# 08-USB_TF.net
KiCad netlist of a schematic drawn in Altium Designer
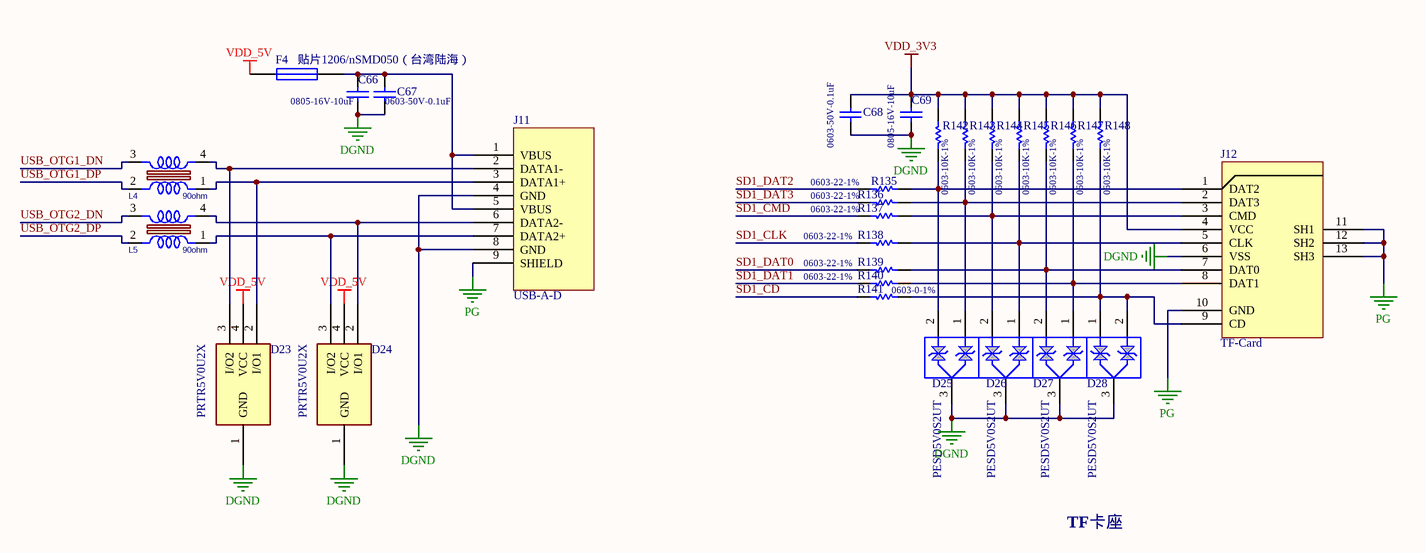
[diagram p0: 08-USB&TF.SchDoc]

(export (version "E")
  (design (tool "Eeschema 10.0.6"))
  (components
    (comp (ref "C66")
      (value "0805-16V-10uF")
      (footprint "0805C")
      (description "Capacitor")
      (fields (field (name "PUBLISHER") "Altium Limited"))
      (libsource (lib "Miscellaneous Devices") (part "Cap"))
    )
    (comp (ref "C67")
      (value "0603-50V-0.1uF")
      (footprint "0603C")
      (description "Capacitor")
      (fields (field (name "PUBLISHER") "Altium Limited"))
      (libsource (lib "Miscellaneous Devices") (part "Cap"))
    )
    (comp (ref "C68")
      (value "0603-50V-0.1uF")
      (footprint "0603C")
      (description "Capacitor")
      (fields (field (name "PUBLISHER") "Altium Limited"))
      (libsource (lib "Miscellaneous Devices") (part "Cap"))
    )
    (comp (ref "C69")
      (value "0805-16V-10uF")
      (footprint "0805C")
      (description "Capacitor")
      (fields (field (name "PUBLISHER") "Altium Limited"))
      (libsource (lib "Miscellaneous Devices") (part "Cap"))
    )
    (comp (ref "D23")
      (value "PRTR5V0U2X")
      (footprint "SOT-143")
      (description "PRTR5V0U2X,SOT-143B,NXP,RoHS")
      (libsource (lib "ErpMaterialData") (part "PRTR5V0U2X"))
    )
    (comp (ref "D24")
      (value "PRTR5V0U2X")
      (footprint "SOT-143")
      (description "PRTR5V0U2X,SOT-143B,NXP,RoHS")
      (libsource (lib "ErpMaterialData") (part "PRTR5V0U2X"))
    )
    (comp (ref "D25")
      (value "PESD5V0S2UT")
      (footprint "SOT-23")
      (description "TVS protect")
      (libsource (lib "*") (part "NUP2105L"))
    )
    (comp (ref "D26")
      (value "PESD5V0S2UT")
      (footprint "SOT-23")
      (description "TVS protect")
      (libsource (lib "*") (part "NUP2105L"))
    )
    (comp (ref "D27")
      (value "PESD5V0S2UT")
      (footprint "SOT-23")
      (description "TVS protect")
      (libsource (lib "*") (part "NUP2105L"))
    )
    (comp (ref "D28")
      (value "PESD5V0S2UT")
      (footprint "SOT-23")
      (description "TVS protect")
      (libsource (lib "*") (part "NUP2105L"))
    )
    (comp (ref "F4")
      (value "贴片1206/nSMD050（台湾陆海）")
      (footprint "1206F")
      (description "Fuse")
      (fields (field (name "PUBLISHER") "Altium Limited"))
      (libsource (lib "Miscellaneous Devices") (part "Fuse 1"))
    )
    (comp (ref "J11") (value "USB-A-D") (footprint "USB-AF-D") (libsource (lib "SCH-QQ") (part "USB-A-D")))
    (comp (ref "J12") (value "TF-Card") (footprint "SDCARD-M") (libsource (lib "Demos") (part "TF01A")))
    (comp (ref "L4")
      (value "90ohm")
      (footprint "indcm-sdcw2012")
      (description "共模电感")
      (libsource (lib "*") (part "Common Choke"))
    )
    (comp (ref "L5")
      (value "90ohm")
      (footprint "indcm-sdcw2012")
      (description "共模电感")
      (libsource (lib "*") (part "Common Choke"))
    )
    (comp (ref "R135")
      (value "0603-22-1%")
      (footprint "0603R")
      (description "Resistor")
      (fields (field (name "PUBLISHER") "Altium Limited"))
      (libsource (lib "Miscellaneous Devices") (part "Res1"))
    )
    (comp (ref "R136")
      (value "0603-22-1%")
      (footprint "0603R")
      (description "Resistor")
      (fields (field (name "PUBLISHER") "Altium Limited"))
      (libsource (lib "Miscellaneous Devices") (part "Res1"))
    )
    (comp (ref "R137")
      (value "0603-22-1%")
      (footprint "0603R")
      (description "Resistor")
      (fields (field (name "PUBLISHER") "Altium Limited"))
      (libsource (lib "Miscellaneous Devices") (part "Res1"))
    )
    (comp (ref "R138")
      (value "0603-22-1%")
      (footprint "0603R")
      (description "Resistor")
      (fields (field (name "PUBLISHER") "Altium Limited"))
      (libsource (lib "Miscellaneous Devices") (part "Res1"))
    )
    (comp (ref "R139")
      (value "0603-22-1%")
      (footprint "0603R")
      (description "Resistor")
      (fields (field (name "PUBLISHER") "Altium Limited"))
      (libsource (lib "Miscellaneous Devices") (part "Res1"))
    )
    (comp (ref "R140")
      (value "0603-22-1%")
      (footprint "0603R")
      (description "Resistor")
      (fields (field (name "PUBLISHER") "Altium Limited"))
      (libsource (lib "Miscellaneous Devices") (part "Res1"))
    )
    (comp (ref "R141")
      (value "0603-0-1%")
      (footprint "0603R")
      (description "Resistor")
      (fields (field (name "PUBLISHER") "Altium Limited"))
      (libsource (lib "Miscellaneous Devices") (part "Res1"))
    )
    (comp (ref "R142")
      (value "0603-10K-1%")
      (footprint "0603R")
      (description "Resistor")
      (fields (field (name "PUBLISHER") "Altium Limited"))
      (libsource (lib "Miscellaneous Devices") (part "Res1"))
    )
    (comp (ref "R143")
      (value "0603-10K-1%")
      (footprint "0603R")
      (description "Resistor")
      (fields (field (name "PUBLISHER") "Altium Limited"))
      (libsource (lib "Miscellaneous Devices") (part "Res1"))
    )
    (comp (ref "R144")
      (value "0603-10K-1%")
      (footprint "0603R")
      (description "Resistor")
      (fields (field (name "PUBLISHER") "Altium Limited"))
      (libsource (lib "Miscellaneous Devices") (part "Res1"))
    )
    (comp (ref "R145")
      (value "0603-10K-1%")
      (footprint "0603R")
      (description "Resistor")
      (fields (field (name "PUBLISHER") "Altium Limited"))
      (libsource (lib "Miscellaneous Devices") (part "Res1"))
    )
    (comp (ref "R146")
      (value "0603-10K-1%")
      (footprint "0603R")
      (description "Resistor")
      (fields (field (name "PUBLISHER") "Altium Limited"))
      (libsource (lib "Miscellaneous Devices") (part "Res1"))
    )
    (comp (ref "R147")
      (value "0603-10K-1%")
      (footprint "0603R")
      (description "Resistor")
      (fields (field (name "PUBLISHER") "Altium Limited"))
      (libsource (lib "Miscellaneous Devices") (part "Res1"))
    )
    (comp (ref "R148")
      (value "0603-10K-1%")
      (footprint "0603R")
      (description "Resistor")
      (fields (field (name "PUBLISHER") "Altium Limited"))
      (libsource (lib "Miscellaneous Devices") (part "Res1"))
    )
  )
  (nets
    (net (code "1") (name "/SD1_CD") (class "Default")
      (node (ref "R141") (pin "2") (pinfunction "2_2") (pintype "passive"))
    )
    (net (code "2") (name "/SD1_CLK") (class "Default")
      (node (ref "R138") (pin "2") (pinfunction "2_2") (pintype "passive"))
    )
    (net (code "3") (name "/SD1_CMD") (class "Default")
      (node (ref "R137") (pin "2") (pinfunction "2_2") (pintype "passive"))
    )
    (net (code "4") (name "/SD1_DAT0") (class "Default")
      (node (ref "R139") (pin "2") (pinfunction "2_2") (pintype "passive"))
    )
    (net (code "5") (name "/SD1_DAT1") (class "Default")
      (node (ref "R140") (pin "2") (pinfunction "2_2") (pintype "passive"))
    )
    (net (code "6") (name "/SD1_DAT2") (class "Default")
      (node (ref "R135") (pin "2") (pinfunction "2_2") (pintype "passive"))
    )
    (net (code "7") (name "/SD1_DAT3") (class "Default")
      (node (ref "R136") (pin "2") (pinfunction "2_2") (pintype "passive"))
    )
    (net (code "8") (name "/USB_OTG1_DN") (class "Default")
      (node (ref "L4") (pin "3") (pinfunction "3_3") (pintype "passive"))
    )
    (net (code "9") (name "/USB_OTG1_DP") (class "Default")
      (node (ref "L4") (pin "2") (pinfunction "2_2") (pintype "passive"))
    )
    (net (code "10") (name "/USB_OTG2_DN") (class "Default")
      (node (ref "L5") (pin "3") (pinfunction "3_3") (pintype "passive"))
    )
    (net (code "11") (name "/USB_OTG2_DP") (class "Default")
      (node (ref "L5") (pin "2") (pinfunction "2_2") (pintype "passive"))
    )
    (net (code "12") (name "DGND") (class "Default")
      (node (ref "C66") (pin "2") (pinfunction "2_2") (pintype "passive"))
      (node (ref "C67") (pin "2") (pinfunction "2_2") (pintype "passive"))
      (node (ref "C68") (pin "2") (pinfunction "2_2") (pintype "passive"))
      (node (ref "C69") (pin "2") (pinfunction "2_2") (pintype "passive"))
      (node (ref "D23") (pin "1") (pinfunction "GND_1") (pintype "passive"))
      (node (ref "D24") (pin "1") (pinfunction "GND_1") (pintype "passive"))
      (node (ref "D25") (pin "3") (pinfunction "3_3") (pintype "passive"))
      (node (ref "D26") (pin "3") (pinfunction "3_3") (pintype "passive"))
      (node (ref "D27") (pin "3") (pinfunction "3_3") (pintype "passive"))
      (node (ref "D28") (pin "3") (pinfunction "3_3") (pintype "passive"))
      (node (ref "J11") (pin "4") (pinfunction "GND_4") (pintype "passive"))
      (node (ref "J11") (pin "8") (pinfunction "GND_8") (pintype "passive"))
      (node (ref "J12") (pin "6") (pinfunction "VSS_6") (pintype "passive"))
    )
    (net (code "13") (name "Net-(C66-Pad1)") (class "Default")
      (node (ref "C66") (pin "1") (pinfunction "1_1") (pintype "passive"))
      (node (ref "C67") (pin "1") (pinfunction "1_1") (pintype "passive"))
      (node (ref "F4") (pin "2") (pinfunction "2_2") (pintype "passive"))
      (node (ref "J11") (pin "1") (pinfunction "VBUS_1") (pintype "passive"))
      (node (ref "J11") (pin "5") (pinfunction "VBUS_5") (pintype "passive"))
    )
    (net (code "14") (name "Net-(D23-I{slash}O1)") (class "Default")
      (node (ref "D23") (pin "2") (pinfunction "I/O1_2") (pintype "passive"))
      (node (ref "J11") (pin "3") (pinfunction "DATA1+_3") (pintype "passive"))
      (node (ref "L4") (pin "1") (pinfunction "1_1") (pintype "passive"))
    )
    (net (code "15") (name "Net-(D23-I{slash}O2)") (class "Default")
      (node (ref "D23") (pin "3") (pinfunction "I/O2_3") (pintype "passive"))
      (node (ref "J11") (pin "2") (pinfunction "DATA1-_2") (pintype "passive"))
      (node (ref "L4") (pin "4") (pinfunction "4_4") (pintype "passive"))
    )
    (net (code "16") (name "Net-(D24-I{slash}O1)") (class "Default")
      (node (ref "D24") (pin "2") (pinfunction "I/O1_2") (pintype "passive"))
      (node (ref "J11") (pin "6") (pinfunction "DATA2-_6") (pintype "passive"))
      (node (ref "L5") (pin "4") (pinfunction "4_4") (pintype "passive"))
    )
    (net (code "17") (name "Net-(D24-I{slash}O2)") (class "Default")
      (node (ref "D24") (pin "3") (pinfunction "I/O2_3") (pintype "passive"))
      (node (ref "J11") (pin "7") (pinfunction "DATA2+_7") (pintype "passive"))
      (node (ref "L5") (pin "1") (pinfunction "1_1") (pintype "passive"))
    )
    (net (code "18") (name "Net-(J12-CD)") (class "Default")
      (node (ref "D28") (pin "1") (pinfunction "1_1") (pintype "passive"))
      (node (ref "D28") (pin "2") (pinfunction "2_2") (pintype "passive"))
      (node (ref "J12") (pin "9") (pinfunction "CD_9") (pintype "passive"))
      (node (ref "R141") (pin "1") (pinfunction "1_1") (pintype "passive"))
      (node (ref "R148") (pin "2") (pinfunction "2_2") (pintype "passive"))
    )
    (net (code "19") (name "Net-(J12-CLK)") (class "Default")
      (node (ref "D26") (pin "1") (pinfunction "1_1") (pintype "passive"))
      (node (ref "J12") (pin "5") (pinfunction "CLK_5") (pintype "passive"))
      (node (ref "R138") (pin "1") (pinfunction "1_1") (pintype "passive"))
      (node (ref "R145") (pin "2") (pinfunction "2_2") (pintype "passive"))
    )
    (net (code "20") (name "Net-(J12-CMD)") (class "Default")
      (node (ref "D26") (pin "2") (pinfunction "2_2") (pintype "passive"))
      (node (ref "J12") (pin "3") (pinfunction "CMD_3") (pintype "passive"))
      (node (ref "R137") (pin "1") (pinfunction "1_1") (pintype "passive"))
      (node (ref "R144") (pin "2") (pinfunction "2_2") (pintype "passive"))
    )
    (net (code "21") (name "Net-(J12-DAT0)") (class "Default")
      (node (ref "D27") (pin "2") (pinfunction "2_2") (pintype "passive"))
      (node (ref "J12") (pin "7") (pinfunction "DAT0_7") (pintype "passive"))
      (node (ref "R139") (pin "1") (pinfunction "1_1") (pintype "passive"))
      (node (ref "R146") (pin "2") (pinfunction "2_2") (pintype "passive"))
    )
    (net (code "22") (name "Net-(J12-DAT1)") (class "Default")
      (node (ref "D27") (pin "1") (pinfunction "1_1") (pintype "passive"))
      (node (ref "J12") (pin "8") (pinfunction "DAT1_8") (pintype "passive"))
      (node (ref "R140") (pin "1") (pinfunction "1_1") (pintype "passive"))
      (node (ref "R147") (pin "2") (pinfunction "2_2") (pintype "passive"))
    )
    (net (code "23") (name "Net-(J12-DAT2)") (class "Default")
      (node (ref "D25") (pin "2") (pinfunction "2_2") (pintype "passive"))
      (node (ref "J12") (pin "1") (pinfunction "DAT2_1") (pintype "passive"))
      (node (ref "R135") (pin "1") (pinfunction "1_1") (pintype "passive"))
      (node (ref "R142") (pin "2") (pinfunction "2_2") (pintype "passive"))
    )
    (net (code "24") (name "Net-(J12-DAT3)") (class "Default")
      (node (ref "D25") (pin "1") (pinfunction "1_1") (pintype "passive"))
      (node (ref "J12") (pin "2") (pinfunction "DAT3_2") (pintype "passive"))
      (node (ref "R136") (pin "1") (pinfunction "1_1") (pintype "passive"))
      (node (ref "R143") (pin "2") (pinfunction "2_2") (pintype "passive"))
    )
    (net (code "25") (name "PG") (class "Default")
      (node (ref "J11") (pin "9") (pinfunction "SHIELD_9") (pintype "passive"))
      (node (ref "J12") (pin "10") (pinfunction "GND_10") (pintype "passive"))
      (node (ref "J12") (pin "11") (pinfunction "SH1_11") (pintype "passive"))
      (node (ref "J12") (pin "12") (pinfunction "SH2_12") (pintype "passive"))
      (node (ref "J12") (pin "13") (pinfunction "SH3_13") (pintype "passive"))
    )
    (net (code "26") (name "VDD_3V3") (class "Default")
      (node (ref "C68") (pin "1") (pinfunction "1_1") (pintype "passive"))
      (node (ref "C69") (pin "1") (pinfunction "1_1") (pintype "passive"))
      (node (ref "J12") (pin "4") (pinfunction "VCC_4") (pintype "passive"))
      (node (ref "R142") (pin "1") (pinfunction "1_1") (pintype "passive"))
      (node (ref "R143") (pin "1") (pinfunction "1_1") (pintype "passive"))
      (node (ref "R144") (pin "1") (pinfunction "1_1") (pintype "passive"))
      (node (ref "R145") (pin "1") (pinfunction "1_1") (pintype "passive"))
      (node (ref "R146") (pin "1") (pinfunction "1_1") (pintype "passive"))
      (node (ref "R147") (pin "1") (pinfunction "1_1") (pintype "passive"))
      (node (ref "R148") (pin "1") (pinfunction "1_1") (pintype "passive"))
    )
    (net (code "27") (name "VDD_5V") (class "Default")
      (node (ref "D23") (pin "4") (pinfunction "VCC_4") (pintype "passive"))
      (node (ref "D24") (pin "4") (pinfunction "VCC_4") (pintype "passive"))
      (node (ref "F4") (pin "1") (pinfunction "1_1") (pintype "passive"))
    )
  )
)
